# scb.net
KiCad netlist of a schematic drawn in Altium Designer
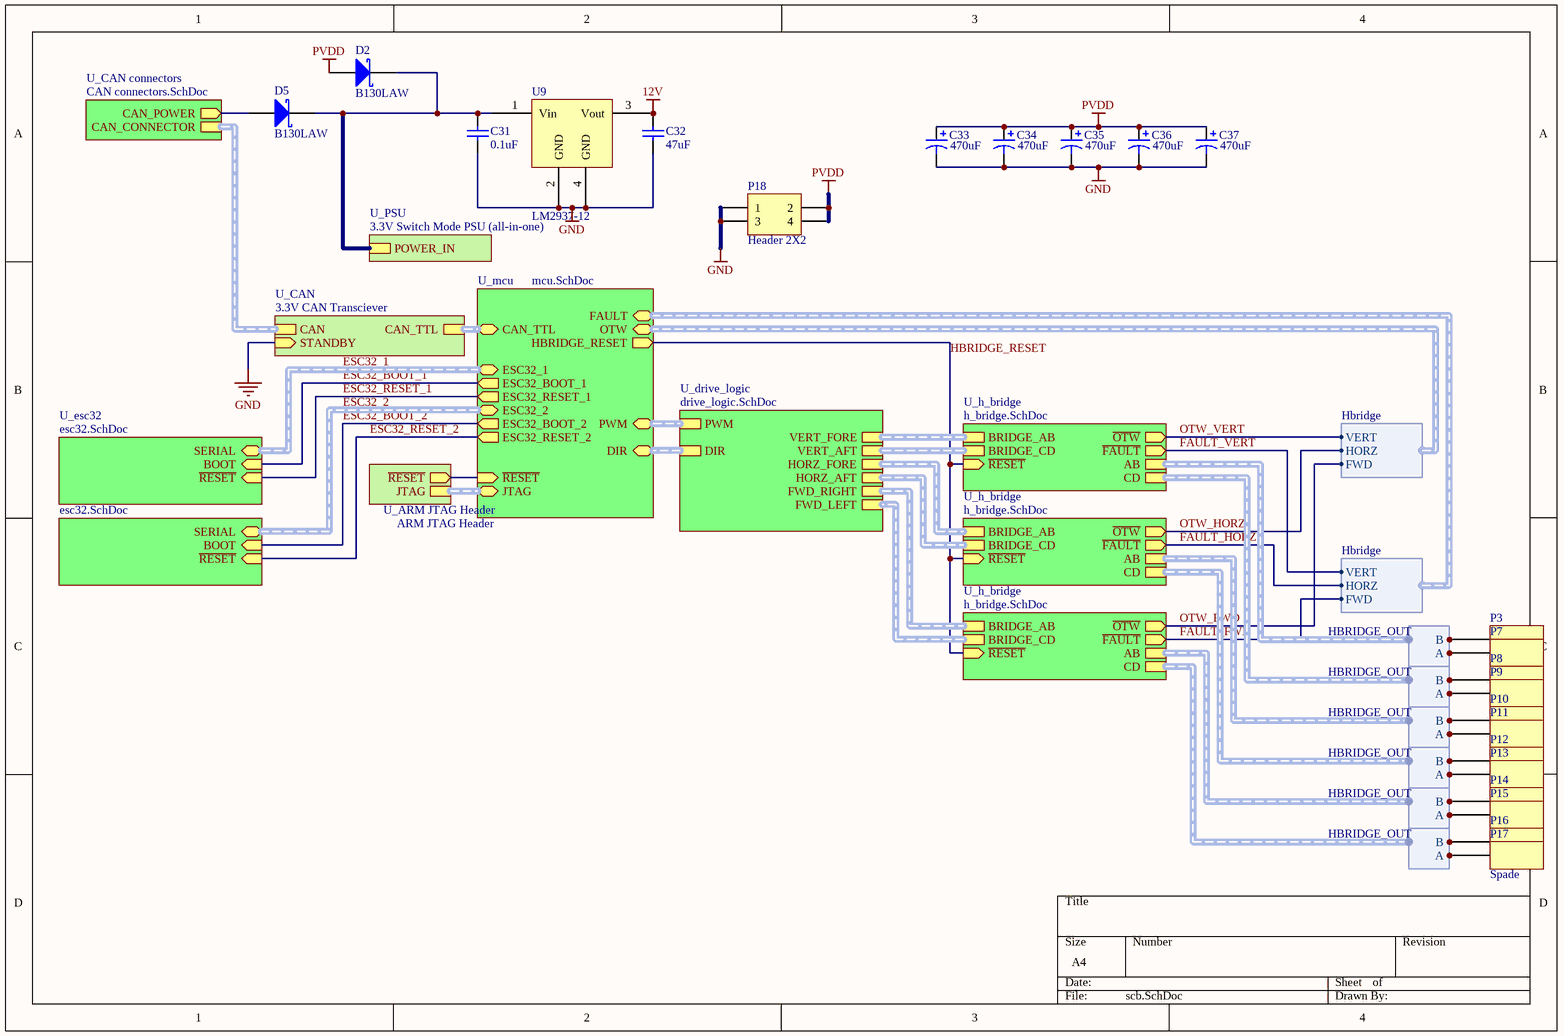
[diagram p0: scb.SchDoc]

(export (version "E")
  (design (tool "Eeschema 10.0.6"))
  (components
    (comp (ref "C31")
      (value "0.1uF")
      (footprint "C0603")
      (description "Capacitor")
      (fields (field (name "Comment") "Cap"))
      (libsource (lib "Miscellaneous Devices") (part "Cap"))
    )
    (comp (ref "C32")
      (value "47uF")
      (footprint "C0805")
      (description "Capacitor")
      (fields (field (name "Comment") "Cap"))
      (libsource (lib "Miscellaneous Devices") (part "Cap"))
    )
    (comp (ref "C33")
      (value "470uF")
      (footprint "8mm SMD Can")
      (description "Polarized Capacitor (Radial)")
      (fields (field (name "Comment") "Cap Pol1") (field (name "PUBLISHER") "Altium Limited"))
      (libsource (lib "Miscellaneous Devices") (part "Cap Pol1"))
    )
    (comp (ref "C34")
      (value "470uF")
      (footprint "8mm SMD Can")
      (description "Polarized Capacitor (Radial)")
      (fields (field (name "Comment") "Cap Pol1") (field (name "PUBLISHER") "Altium Limited"))
      (libsource (lib "Miscellaneous Devices") (part "Cap Pol1"))
    )
    (comp (ref "C35")
      (value "470uF")
      (footprint "8mm SMD Can")
      (description "Polarized Capacitor (Radial)")
      (fields (field (name "Comment") "Cap Pol1") (field (name "PUBLISHER") "Altium Limited"))
      (libsource (lib "Miscellaneous Devices") (part "Cap Pol1"))
    )
    (comp (ref "C36")
      (value "470uF")
      (footprint "8mm SMD Can")
      (description "Polarized Capacitor (Radial)")
      (fields (field (name "Comment") "Cap Pol1") (field (name "PUBLISHER") "Altium Limited"))
      (libsource (lib "Miscellaneous Devices") (part "Cap Pol1"))
    )
    (comp (ref "C37")
      (value "470uF")
      (footprint "8mm SMD Can")
      (description "Polarized Capacitor (Radial)")
      (fields (field (name "Comment") "Cap Pol1") (field (name "PUBLISHER") "Altium Limited"))
      (libsource (lib "Miscellaneous Devices") (part "Cap Pol1"))
    )
    (comp (ref "D2")
      (value "B130LAW")
      (footprint "SOD-123")
      (description "Schottky Diode")
      (fields (field (name "PUBLISHER") "Altium Limited"))
      (libsource (lib "Miscellaneous Devices") (part "D Schottky"))
    )
    (comp (ref "D5")
      (value "B130LAW")
      (footprint "SOD-123")
      (description "Schottky Diode")
      (fields (field (name "PUBLISHER") "Altium Limited"))
      (libsource (lib "Miscellaneous Devices") (part "D Schottky"))
    )
    (comp (ref "P3")
      (value "Spade")
      (footprint "3866A")
      (description "Space connector")
      (libsource (lib "3866A68 (spade connectors)") (part "3866A"))
    )
    (comp (ref "P7")
      (value "Spade")
      (footprint "3866A")
      (description "Space connector")
      (libsource (lib "3866A68 (spade connectors)") (part "3866A"))
    )
    (comp (ref "P8")
      (value "Spade")
      (footprint "3866A")
      (description "Space connector")
      (libsource (lib "3866A68 (spade connectors)") (part "3866A"))
    )
    (comp (ref "P9")
      (value "Spade")
      (footprint "3866A")
      (description "Space connector")
      (libsource (lib "3866A68 (spade connectors)") (part "3866A"))
    )
    (comp (ref "P10")
      (value "Spade")
      (footprint "3866A")
      (description "Space connector")
      (libsource (lib "3866A68 (spade connectors)") (part "3866A"))
    )
    (comp (ref "P11")
      (value "Spade")
      (footprint "3866A")
      (description "Space connector")
      (libsource (lib "3866A68 (spade connectors)") (part "3866A"))
    )
    (comp (ref "P12")
      (value "Spade")
      (footprint "3866A")
      (description "Space connector")
      (libsource (lib "3866A68 (spade connectors)") (part "3866A"))
    )
    (comp (ref "P13")
      (value "Spade")
      (footprint "3866A")
      (description "Space connector")
      (libsource (lib "3866A68 (spade connectors)") (part "3866A"))
    )
    (comp (ref "P14")
      (value "Spade")
      (footprint "3866A")
      (description "Space connector")
      (libsource (lib "3866A68 (spade connectors)") (part "3866A"))
    )
    (comp (ref "P15")
      (value "Spade")
      (footprint "3866A")
      (description "Space connector")
      (libsource (lib "3866A68 (spade connectors)") (part "3866A"))
    )
    (comp (ref "P16")
      (value "Spade")
      (footprint "3866A")
      (description "Space connector")
      (libsource (lib "3866A68 (spade connectors)") (part "3866A"))
    )
    (comp (ref "P17")
      (value "Spade")
      (footprint "3866A")
      (description "Space connector")
      (libsource (lib "3866A68 (spade connectors)") (part "3866A"))
    )
    (comp (ref "P18")
      (value "Header 2X2")
      (footprint "39-28-1043")
      (description "Header, 2-Pin, Dual row")
      (fields (field (name "PUBLISHER") "Altium Limited"))
      (libsource (lib "Miscellaneous Connectors") (part "Header 2X2"))
    )
    (comp (ref "U9")
      (value "LM2937-12")
      (footprint "SOT230P700X180-4N")
      (libsource (lib "LM2937") (part "LM2937"))
    )
  )
  (nets
    (net (code "12") (name "/CAN_POWER") (class "Default")
      (node (ref "D5") (pin "1") (pinfunction "A_1") (pintype "passive"))
    )
    (net (code "27") (name "/POWER_IN") (class "Default")
      (node (ref "C31") (pin "1") (pinfunction "1_1") (pintype "passive"))
      (node (ref "D2") (pin "2") (pinfunction "K_2") (pintype "passive"))
      (node (ref "D5") (pin "2") (pinfunction "K_2") (pintype "passive"))
      (node (ref "U9") (pin "1") (pinfunction "Vin_1") (pintype "passive"))
    )
    (net (code "34") (name "12V") (class "Default")
      (node (ref "C32") (pin "1") (pinfunction "1_1") (pintype "passive"))
      (node (ref "U9") (pin "3") (pinfunction "Vout_3") (pintype "power_in"))
    )
    (net (code "35") (name "GND") (class "Default")
      (node (ref "C31") (pin "2") (pinfunction "2_2") (pintype "passive"))
      (node (ref "C32") (pin "2") (pinfunction "2_2") (pintype "passive"))
      (node (ref "C33") (pin "2") (pinfunction "2_2") (pintype "passive"))
      (node (ref "C34") (pin "2") (pinfunction "2_2") (pintype "passive"))
      (node (ref "C35") (pin "2") (pinfunction "2_2") (pintype "passive"))
      (node (ref "C36") (pin "2") (pinfunction "2_2") (pintype "passive"))
      (node (ref "C37") (pin "2") (pinfunction "2_2") (pintype "passive"))
      (node (ref "P18") (pin "1") (pinfunction "1_1") (pintype "passive"))
      (node (ref "P18") (pin "3") (pinfunction "3_3") (pintype "passive"))
      (node (ref "U9") (pin "2") (pinfunction "GND_2") (pintype "power_in"))
      (node (ref "U9") (pin "4") (pinfunction "GND_4") (pintype "power_in"))
    )
    (net (code "36") (name "Net-(P3-32)") (class "Default")
      (node (ref "P3") (pin "1") (pinfunction "33_1") (pintype "passive"))
      (node (ref "P3") (pin "2") (pinfunction "32_2") (pintype "passive"))
    )
    (net (code "37") (name "Net-(P7-32)") (class "Default")
      (node (ref "P7") (pin "1") (pinfunction "33_1") (pintype "passive"))
      (node (ref "P7") (pin "2") (pinfunction "32_2") (pintype "passive"))
    )
    (net (code "38") (name "Net-(P8-32)") (class "Default")
      (node (ref "P8") (pin "1") (pinfunction "33_1") (pintype "passive"))
      (node (ref "P8") (pin "2") (pinfunction "32_2") (pintype "passive"))
    )
    (net (code "39") (name "Net-(P9-32)") (class "Default")
      (node (ref "P9") (pin "1") (pinfunction "33_1") (pintype "passive"))
      (node (ref "P9") (pin "2") (pinfunction "32_2") (pintype "passive"))
    )
    (net (code "40") (name "Net-(P10-32)") (class "Default")
      (node (ref "P10") (pin "1") (pinfunction "33_1") (pintype "passive"))
      (node (ref "P10") (pin "2") (pinfunction "32_2") (pintype "passive"))
    )
    (net (code "41") (name "Net-(P11-32)") (class "Default")
      (node (ref "P11") (pin "1") (pinfunction "33_1") (pintype "passive"))
      (node (ref "P11") (pin "2") (pinfunction "32_2") (pintype "passive"))
    )
    (net (code "42") (name "Net-(P12-32)") (class "Default")
      (node (ref "P12") (pin "1") (pinfunction "33_1") (pintype "passive"))
      (node (ref "P12") (pin "2") (pinfunction "32_2") (pintype "passive"))
    )
    (net (code "43") (name "Net-(P13-32)") (class "Default")
      (node (ref "P13") (pin "1") (pinfunction "33_1") (pintype "passive"))
      (node (ref "P13") (pin "2") (pinfunction "32_2") (pintype "passive"))
    )
    (net (code "44") (name "Net-(P14-32)") (class "Default")
      (node (ref "P14") (pin "1") (pinfunction "33_1") (pintype "passive"))
      (node (ref "P14") (pin "2") (pinfunction "32_2") (pintype "passive"))
    )
    (net (code "45") (name "Net-(P15-32)") (class "Default")
      (node (ref "P15") (pin "1") (pinfunction "33_1") (pintype "passive"))
      (node (ref "P15") (pin "2") (pinfunction "32_2") (pintype "passive"))
    )
    (net (code "46") (name "Net-(P16-32)") (class "Default")
      (node (ref "P16") (pin "1") (pinfunction "33_1") (pintype "passive"))
      (node (ref "P16") (pin "2") (pinfunction "32_2") (pintype "passive"))
    )
    (net (code "47") (name "Net-(P17-32)") (class "Default")
      (node (ref "P17") (pin "1") (pinfunction "33_1") (pintype "passive"))
      (node (ref "P17") (pin "2") (pinfunction "32_2") (pintype "passive"))
    )
    (net (code "48") (name "PVDD") (class "Default")
      (node (ref "C33") (pin "1") (pinfunction "1_1") (pintype "passive"))
      (node (ref "C34") (pin "1") (pinfunction "1_1") (pintype "passive"))
      (node (ref "C35") (pin "1") (pinfunction "1_1") (pintype "passive"))
      (node (ref "C36") (pin "1") (pinfunction "1_1") (pintype "passive"))
      (node (ref "C37") (pin "1") (pinfunction "1_1") (pintype "passive"))
      (node (ref "D2") (pin "1") (pinfunction "A_1") (pintype "passive"))
      (node (ref "P18") (pin "2") (pinfunction "2_2") (pintype "passive"))
      (node (ref "P18") (pin "4") (pinfunction "4_4") (pintype "passive"))
    )
  )
)
